# acs711-shield.net
KiCad netlist of a schematic drawn in EAGLE
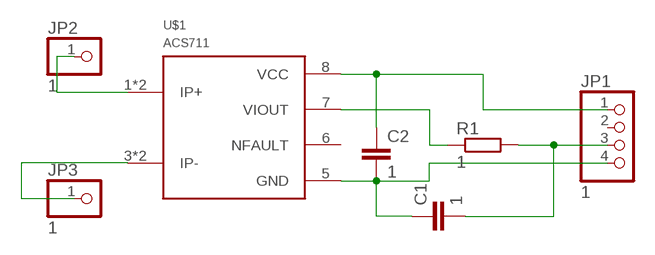
[diagram p0: schematic, sheet 1]

(export (version "E")
  (design (tool "Eeschema 10.0.6"))
  (components
    (comp (ref "C1")
      (value "1")
      (footprint "eagle-import:C0402")
      (libsource (lib "eagle-import") (part "C-EUC0402"))
    )
    (comp (ref "C2")
      (value "1")
      (footprint "eagle-import:C0402")
      (libsource (lib "eagle-import") (part "C-EUC0402"))
    )
    (comp (ref "JP1")
      (value "1")
      (footprint "eagle-import:1X04")
      (libsource (lib "eagle-import") (part "PINHD-1X4"))
    )
    (comp (ref "JP2")
      (value "1")
      (footprint "eagle-import:1X01")
      (libsource (lib "eagle-import") (part "PINHD-1X1"))
    )
    (comp (ref "JP3")
      (value "1")
      (footprint "eagle-import:1X01")
      (libsource (lib "eagle-import") (part "PINHD-1X1"))
    )
    (comp (ref "R1")
      (value "1")
      (footprint "eagle-import:R0402")
      (libsource (lib "eagle-import") (part "R-EU_R0402"))
    )
    (comp (ref "U$1")
      (value "ACS711")
      (footprint "eagle-import:SOIC8")
      (libsource (lib "eagle-import") (part "ACS711"))
    )
  )
  (nets
    (net (code "1") (name "Net-(C1-Pad2)") (class "Default")
      (node (ref "C1") (pin "2") (pinfunction "2_2") (pintype "passive"))
      (node (ref "JP1") (pin "3") (pinfunction "3_3") (pintype "passive"))
      (node (ref "R1") (pin "2") (pinfunction "2_2") (pintype "passive"))
    )
    (net (code "2") (name "Net-(JP2-Pad1)") (class "Default")
      (node (ref "JP2") (pin "1") (pinfunction "1_1") (pintype "passive"))
      (node (ref "U$1") (pin "1") (pinfunction "IP+_1") (pintype "bidirectional"))
      (node (ref "U$1") (pin "2") (pinfunction "IP+_2") (pintype "bidirectional"))
    )
    (net (code "3") (name "Net-(JP3-Pad1)") (class "Default")
      (node (ref "JP3") (pin "1") (pinfunction "1_1") (pintype "passive"))
      (node (ref "U$1") (pin "3") (pinfunction "IP-_3") (pintype "bidirectional"))
      (node (ref "U$1") (pin "4") (pinfunction "IP-_4") (pintype "bidirectional"))
    )
    (net (code "4") (name "Net-(U$1-GND)") (class "Default")
      (node (ref "C1") (pin "1") (pinfunction "1_1") (pintype "passive"))
      (node (ref "C2") (pin "2") (pinfunction "2_2") (pintype "passive"))
      (node (ref "JP1") (pin "4") (pinfunction "4_4") (pintype "passive"))
      (node (ref "U$1") (pin "5") (pinfunction "GND_5") (pintype "bidirectional"))
    )
    (net (code "5") (name "Net-(U$1-VCC)") (class "Default")
      (node (ref "C2") (pin "1") (pinfunction "1_1") (pintype "passive"))
      (node (ref "JP1") (pin "1") (pinfunction "1_1") (pintype "passive"))
      (node (ref "U$1") (pin "8") (pinfunction "VCC_8") (pintype "bidirectional"))
    )
    (net (code "6") (name "Net-(U$1-VIOUT)") (class "Default")
      (node (ref "R1") (pin "1") (pinfunction "1_1") (pintype "passive"))
      (node (ref "U$1") (pin "7") (pinfunction "VIOUT_7") (pintype "bidirectional"))
    )
    (net (code "7") (name "unconnected-(JP1-Pad2)") (class "Default")
      (node (ref "JP1") (pin "2") (pinfunction "2_2") (pintype "passive"))
    )
    (net (code "8") (name "unconnected-(U$1-NFAULT-Pad6)") (class "Default")
      (node (ref "U$1") (pin "6") (pinfunction "NFAULT_6") (pintype "bidirectional"))
    )
  )
)
